# 13_-_ETHERNET_PHY.net
KiCad netlist of a schematic drawn in Altium Designer
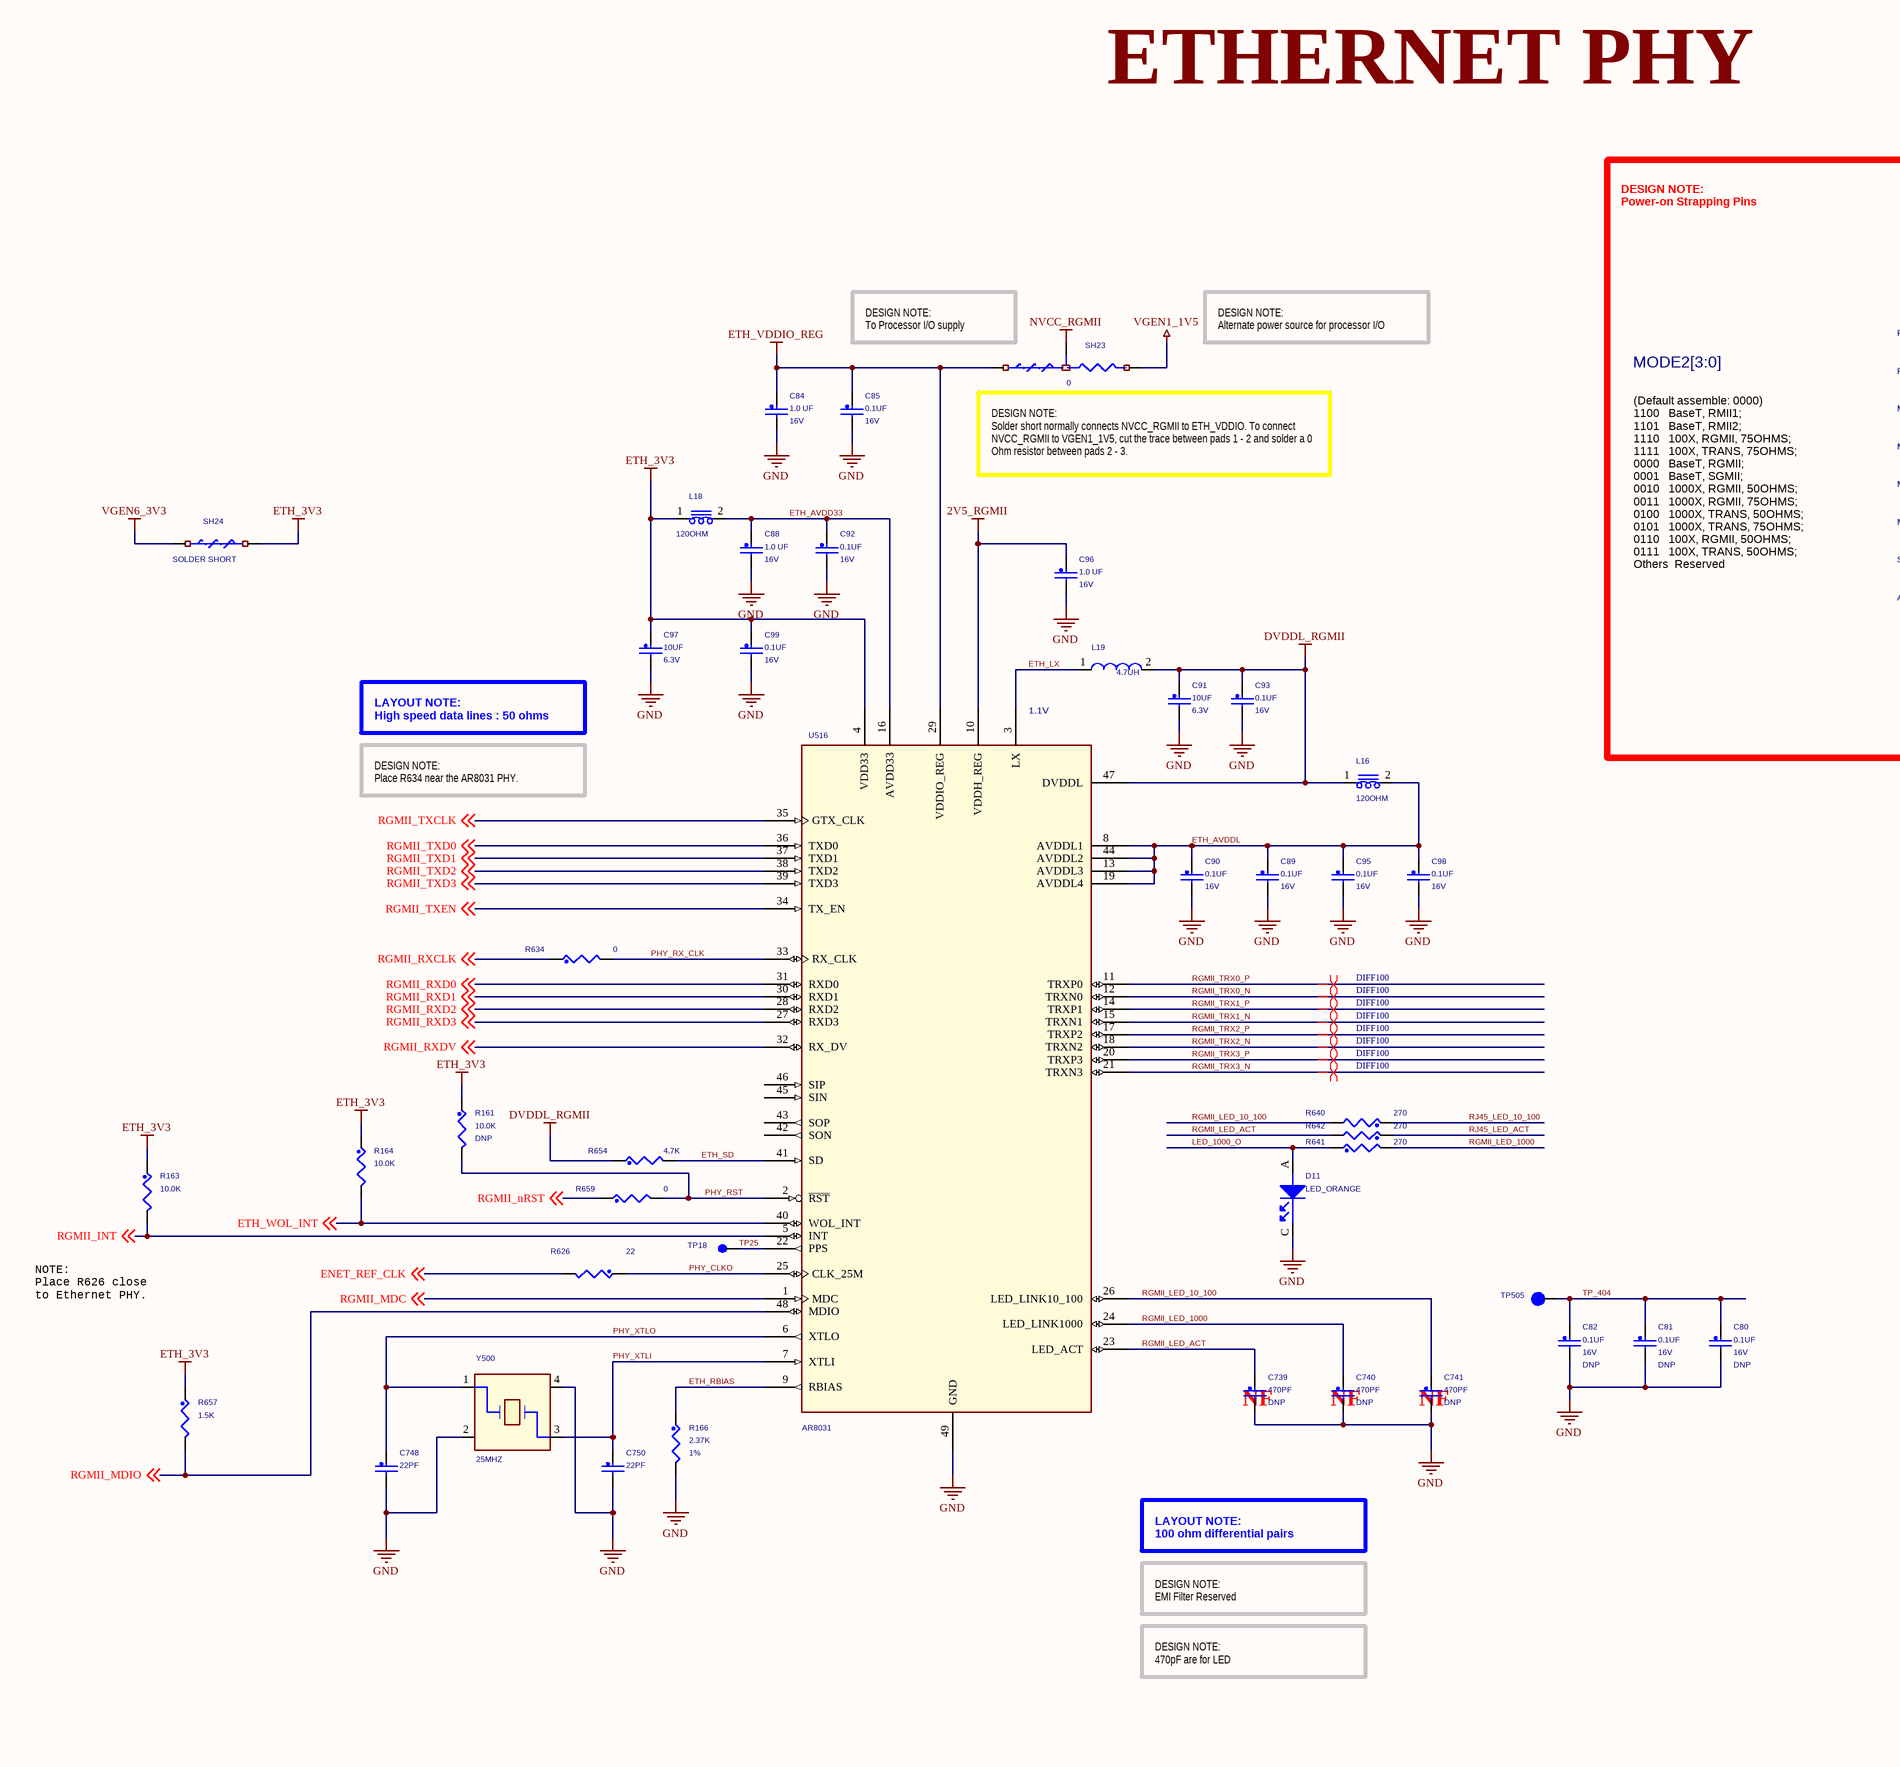
[diagram p0: [13] - ETHERNET PHY.SchDoc, left]
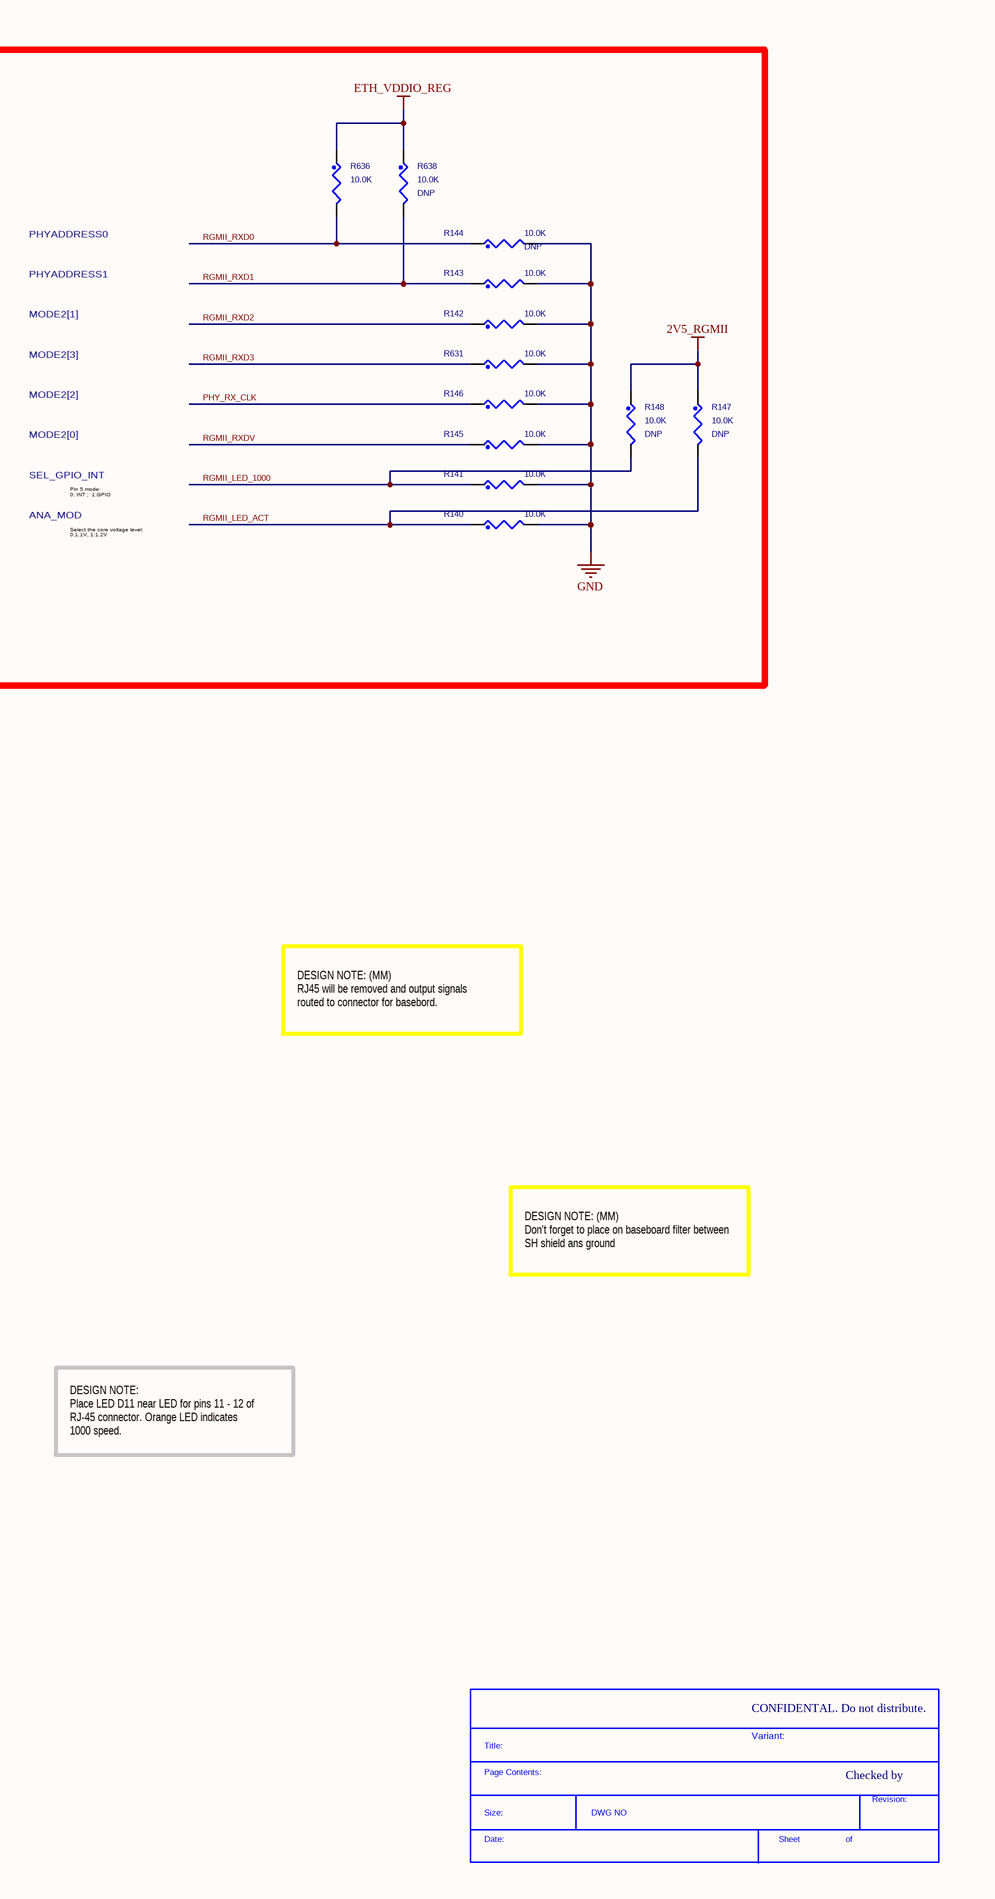
[diagram p1: [13] - ETHERNET PHY.SchDoc, right]

(export (version "E")
  (design (tool "Eeschema 10.0.6"))
  (components
    (comp (ref "*") (value "SDTitleBlock") (libsource (lib "*") (part "SDTitleBlock")))
    (comp (ref "C80")
      (value "0.1UF")
      (description "CAP CER 0.1UF 16V 10% X7R 0402")
      (fields
        (field (name "WVDC") "16V")
        (field (name "ASSY_OPT") "DNP")
        (field (name "TOLERANCE") "10%")
        (field (name "VOLTAGE") "16V")
      )
      (libsource (lib "*") (part "CAP_NP"))
    )
    (comp (ref "C81")
      (value "0.1UF")
      (description "CAP CER 0.1UF 16V 10% X7R 0402")
      (fields
        (field (name "WVDC") "16V")
        (field (name "ASSY_OPT") "DNP")
        (field (name "TOLERANCE") "10%")
        (field (name "VOLTAGE") "16V")
      )
      (libsource (lib "*") (part "CAP_NP"))
    )
    (comp (ref "C82")
      (value "0.1UF")
      (description "CAP CER 0.1UF 16V 10% X7R 0402")
      (fields
        (field (name "WVDC") "16V")
        (field (name "ASSY_OPT") "DNP")
        (field (name "TOLERANCE") "10%")
        (field (name "VOLTAGE") "16V")
      )
      (libsource (lib "*") (part "CAP_NP"))
    )
    (comp (ref "C84")
      (value "1.0 UF")
      (description "CAP CER 1.0UF 16V 10% X7R 0603")
      (fields (field (name "TOLERANCE") "10%") (field (name "WVDC") "16V") (field (name "VOLTAGE") "16V"))
      (libsource (lib "*") (part "CAP_NP"))
    )
    (comp (ref "C85")
      (value "0.1UF")
      (description "CAP CER 0.1UF 16V 10% X7R 0402")
      (fields (field (name "TOLERANCE") "10%") (field (name "WVDC") "16V") (field (name "VOLTAGE") "16V"))
      (libsource (lib "*") (part "CAP_NP"))
    )
    (comp (ref "C88")
      (value "1.0 UF")
      (description "CAP CER 1.0UF 16V 10% X7R 0603")
      (fields (field (name "TOLERANCE") "10%") (field (name "WVDC") "16V") (field (name "VOLTAGE") "16V"))
      (libsource (lib "*") (part "CAP_NP"))
    )
    (comp (ref "C89")
      (value "0.1UF")
      (description "CAP CER 0.1UF 16V 10% X7R 0402")
      (fields (field (name "TOLERANCE") "10%") (field (name "WVDC") "16V") (field (name "VOLTAGE") "16V"))
      (libsource (lib "*") (part "CAP_NP"))
    )
    (comp (ref "C90")
      (value "0.1UF")
      (description "CAP CER 0.1UF 16V 10% X7R 0402")
      (fields (field (name "TOLERANCE") "10%") (field (name "WVDC") "16V") (field (name "VOLTAGE") "16V"))
      (libsource (lib "*") (part "CAP_NP"))
    )
    (comp (ref "C91")
      (value "10UF")
      (description "CAP CER 10UF 6.3V 10% X5R 0603")
      (fields (field (name "TOLERANCE") "10%") (field (name "WVDC") "6.3V") (field (name "VOLTAGE") "6.3V"))
      (libsource (lib "*") (part "CAP_NP"))
    )
    (comp (ref "C92")
      (value "0.1UF")
      (description "CAP CER 0.1UF 16V 10% X7R 0402")
      (fields (field (name "TOLERANCE") "10%") (field (name "WVDC") "16V") (field (name "VOLTAGE") "16V"))
      (libsource (lib "*") (part "CAP_NP"))
    )
    (comp (ref "C93")
      (value "0.1UF")
      (description "CAP CER 0.1UF 16V 10% X7R 0402")
      (fields (field (name "TOLERANCE") "10%") (field (name "WVDC") "16V") (field (name "VOLTAGE") "16V"))
      (libsource (lib "*") (part "CAP_NP"))
    )
    (comp (ref "C95")
      (value "0.1UF")
      (description "CAP CER 0.1UF 16V 10% X7R 0402")
      (fields (field (name "TOLERANCE") "10%") (field (name "WVDC") "16V") (field (name "VOLTAGE") "16V"))
      (libsource (lib "*") (part "CAP_NP"))
    )
    (comp (ref "C96")
      (value "1.0 UF")
      (description "CAP CER 1.0UF 16V 10% X7R 0603")
      (fields (field (name "TOLERANCE") "10%") (field (name "WVDC") "16V") (field (name "VOLTAGE") "16V"))
      (libsource (lib "*") (part "CAP_NP"))
    )
    (comp (ref "C97")
      (value "10UF")
      (description "CAP CER 10UF 6.3V 10% X5R 0603")
      (fields (field (name "TOLERANCE") "10%") (field (name "WVDC") "6.3V") (field (name "VOLTAGE") "6.3V"))
      (libsource (lib "*") (part "CAP_NP"))
    )
    (comp (ref "C98")
      (value "0.1UF")
      (description "CAP CER 0.1UF 16V 10% X7R 0402")
      (fields (field (name "TOLERANCE") "10%") (field (name "WVDC") "16V") (field (name "VOLTAGE") "16V"))
      (libsource (lib "*") (part "CAP_NP"))
    )
    (comp (ref "C99")
      (value "0.1UF")
      (description "CAP CER 0.1UF 16V 10% X7R 0402")
      (fields (field (name "TOLERANCE") "10%") (field (name "WVDC") "16V") (field (name "VOLTAGE") "16V"))
      (libsource (lib "*") (part "CAP_NP"))
    )
    (comp (ref "C739")
      (value "470PF")
      (description "CAP CER 470PF 50V 10% X7R 0402")
      (fields (field (name "TOLERANCE") "10%") (field (name "ASSY_OPT") "DNP") (field (name "VOLTAGE") "50V"))
      (libsource (lib "*") (part "CAP_NP"))
    )
    (comp (ref "C740")
      (value "470PF")
      (description "CAP CER 470PF 50V 10% X7R 0402")
      (fields (field (name "TOLERANCE") "10%") (field (name "ASSY_OPT") "DNP") (field (name "VOLTAGE") "50V"))
      (libsource (lib "*") (part "CAP_NP"))
    )
    (comp (ref "C741")
      (value "470PF")
      (description "CAP CER 470PF 50V 10% X7R 0402")
      (fields (field (name "TOLERANCE") "10%") (field (name "ASSY_OPT") "DNP") (field (name "VOLTAGE") "50V"))
      (libsource (lib "*") (part "CAP_NP"))
    )
    (comp (ref "C748")
      (value "22PF")
      (description "CAP CER 22PF 50V 5% C0G 0402")
      (fields (field (name "TOLERANCE") "5%") (field (name "VOLTAGE") "50V"))
      (libsource (lib "*") (part "CAP_NP"))
    )
    (comp (ref "C750")
      (value "22PF")
      (description "CAP CER 22PF 50V 5% C0G 0402")
      (fields (field (name "TOLERANCE") "5%") (field (name "VOLTAGE") "50V"))
      (libsource (lib "*") (part "CAP_NP"))
    )
    (comp (ref "D11")
      (value "LED_ORANGE")
      (description "LED SUPER BRIGHT ORANGE SMD 0603")
      (libsource (lib "*") (part "LED"))
    )
    (comp (ref "L16")
      (value "120OHM")
      (description "IND FER BEAD 120OHM@100MHZ 2A 25% 0603")
      (fields (field (name "TOLERANCE") "25%"))
      (libsource (lib "*") (part "BEAD_0"))
    )
    (comp (ref "L18")
      (value "120OHM")
      (description "IND FER BEAD 120OHM@100MHZ 2A 25% 0603")
      (fields (field (name "TOLERANCE") "25%"))
      (libsource (lib "*") (part "BEAD_0"))
    )
    (comp (ref "L19")
      (value "4.7UH")
      (description "IND PWR 4.7UH@1MHZ 1A 20% SMD")
      (fields (field (name "TOLERANCE") "20%"))
      (libsource (lib "*") (part "INDUCTOR"))
    )
    (comp (ref "R140")
      (value "10.0K")
      (description "RES MF 10.0K 1/16W 1% 0402")
      (fields (field (name "TOLERANCE") "1%"))
      (libsource (lib "*") (part "RES"))
    )
    (comp (ref "R141")
      (value "10.0K")
      (description "RES MF 10.0K 1/16W 1% 0402")
      (fields (field (name "TOLERANCE") "1%"))
      (libsource (lib "*") (part "RES"))
    )
    (comp (ref "R142")
      (value "10.0K")
      (description "RES MF 10.0K 1/16W 1% 0402")
      (fields (field (name "TOLERANCE") "1%"))
      (libsource (lib "*") (part "RES"))
    )
    (comp (ref "R143")
      (value "10.0K")
      (description "RES MF 10.0K 1/16W 1% 0402")
      (fields (field (name "TOLERANCE") "1%"))
      (libsource (lib "*") (part "RES"))
    )
    (comp (ref "R144")
      (value "10.0K")
      (description "RES MF 10.0K 1/16W 1% 0402")
      (fields (field (name "TOLERANCE") "1%") (field (name "ASSY_OPT") "DNP"))
      (libsource (lib "*") (part "RES"))
    )
    (comp (ref "R145")
      (value "10.0K")
      (description "RES MF 10.0K 1/16W 1% 0402")
      (fields (field (name "TOLERANCE") "1%"))
      (libsource (lib "*") (part "RES"))
    )
    (comp (ref "R146")
      (value "10.0K")
      (description "RES MF 10.0K 1/16W 1% 0402")
      (fields (field (name "TOLERANCE") "1%"))
      (libsource (lib "*") (part "RES"))
    )
    (comp (ref "R147")
      (value "10.0K")
      (description "RES MF 10.0K 1/16W 1% 0402")
      (fields (field (name "TOLERANCE") "1%") (field (name "ASSY_OPT") "DNP"))
      (libsource (lib "*") (part "RES"))
    )
    (comp (ref "R148")
      (value "10.0K")
      (description "RES MF 10.0K 1/16W 1% 0402")
      (fields (field (name "TOLERANCE") "1%") (field (name "ASSY_OPT") "DNP"))
      (libsource (lib "*") (part "RES"))
    )
    (comp (ref "R161")
      (value "10.0K")
      (description "RES MF 10.0K 1/16W 1% 0402")
      (fields (field (name "ASSY_OPT") "DNP") (field (name "TOLERANCE") "1%"))
      (libsource (lib "*") (part "RES"))
    )
    (comp (ref "R163")
      (value "10.0K")
      (description "RES MF 10.0K 1/16W 1% 0402")
      (fields (field (name "TOLERANCE") "1%"))
      (libsource (lib "*") (part "RES"))
    )
    (comp (ref "R164")
      (value "10.0K")
      (description "RES MF 10.0K 1/16W 1% 0402")
      (fields (field (name "TOLERANCE") "1%"))
      (libsource (lib "*") (part "RES"))
    )
    (comp (ref "R166")
      (value "2.37K")
      (description "RES MF 2.37K  1/16W 1% 0402")
      (fields (field (name "TOLERANCE") "1%"))
      (libsource (lib "*") (part "RES"))
    )
    (comp (ref "R626")
      (value "22")
      (description "RES MF 22.0 OHM 1/10W 1% 0603")
      (fields (field (name "TOLERANCE") "1%"))
      (libsource (lib "*") (part "RES"))
    )
    (comp (ref "R631")
      (value "10.0K")
      (description "RES MF 10.0K 1/16W 1% 0402")
      (fields (field (name "TOLERANCE") "1%"))
      (libsource (lib "*") (part "RES"))
    )
    (comp (ref "R634")
      (value "0")
      (description "RES MF ZERO OHM 1/10W -- 0402")
      (libsource (lib "*") (part "RES"))
    )
    (comp (ref "R636")
      (value "10.0K")
      (description "RES MF 10.0K 1/16W 1% 0402")
      (fields (field (name "TOLERANCE") "1%"))
      (libsource (lib "*") (part "RES"))
    )
    (comp (ref "R638")
      (value "10.0K")
      (description "RES MF 10.0K 1/16W 1% 0402")
      (fields (field (name "ASSY_OPT") "DNP") (field (name "TOLERANCE") "1%"))
      (libsource (lib "*") (part "RES"))
    )
    (comp (ref "R640")
      (value "270")
      (description "RES MF 270 OHM 1/16W 5% 0402")
      (fields (field (name "TOLERANCE") "5%"))
      (libsource (lib "*") (part "RES"))
    )
    (comp (ref "R641")
      (value "270")
      (description "RES MF 270 OHM 1/16W 5% 0402")
      (fields (field (name "TOLERANCE") "5%"))
      (libsource (lib "*") (part "RES"))
    )
    (comp (ref "R642")
      (value "270")
      (description "RES MF 270 OHM 1/16W 5% 0402")
      (fields (field (name "TOLERANCE") "5%"))
      (libsource (lib "*") (part "RES"))
    )
    (comp (ref "R654")
      (value "4.7K")
      (description "RES MF 4.70K 1/16W 1% 0402")
      (fields (field (name "TOLERANCE") "1%"))
      (libsource (lib "*") (part "RES"))
    )
    (comp (ref "R657")
      (value "1.5K")
      (description "RES MF 1.50K 1/16W 1% 0402")
      (fields (field (name "TOLERANCE") "1%"))
      (libsource (lib "*") (part "RES"))
    )
    (comp (ref "R659")
      (value "0")
      (description "RES MF ZERO OHM 1/10W -- 0402")
      (libsource (lib "*") (part "RES"))
    )
    (comp (ref "SH23")
      (value "0")
      (description "ZERO OHM CUT TRACE 0603 PADS; NO PART TO ORDER")
      (libsource (lib "*") (part "RES_SHORT-3_1TO2"))
    )
    (comp (ref "SH24")
      (value "SOLDER SHORT")
      (description "SOLDER SHORT 0805  SMT NO PART TO ORDER")
      (libsource (lib "*") (part "RES_SHORT-2"))
    )
    (comp (ref "TP18")
      (value "TEST POINT")
      (description "TEST POINT PAD 35 MIL SMT, NO PART TO ORDER")
      (libsource (lib "*") (part "Test pad"))
    )
    (comp (ref "TP505")
      (value "tpad_020")
      (description "TEST POINT PAD 0.5MM DIA SMT, NO PART TO ORDER")
      (libsource (lib "*") (part "TESTLOOP"))
    )
    (comp (ref "U516")
      (value "AR8031")
      (description "IC XCVR ETHERNET PHY 10/100/1000G-BIT 3.3V QFN48")
      (libsource (lib "*") (part "AR8031_QFN48"))
    )
    (comp (ref "Y500")
      (value "25MHZ")
      (description "XTAL 25MHZ -- -- SMT")
      (libsource (lib "*") (part "XTAL_13Y"))
    )
  )
  (nets
    (net (code "1") (name "/ETH_AVDD33") (class "Default")
      (node (ref "C88") (pin "1") (pinfunction "1_1") (pintype "passive"))
      (node (ref "C92") (pin "1") (pinfunction "1_1") (pintype "passive"))
      (node (ref "L18") (pin "2") (pinfunction "2_2") (pintype "passive"))
      (node (ref "U516") (pin "16") (pinfunction "AVDD33_16") (pintype "power_in"))
    )
    (net (code "2") (name "/ETH_AVDDL") (class "Default")
      (node (ref "C89") (pin "1") (pinfunction "1_1") (pintype "passive"))
      (node (ref "C90") (pin "1") (pinfunction "1_1") (pintype "passive"))
      (node (ref "C95") (pin "1") (pinfunction "1_1") (pintype "passive"))
      (node (ref "C98") (pin "1") (pinfunction "1_1") (pintype "passive"))
      (node (ref "L16") (pin "2") (pinfunction "2_2") (pintype "passive"))
      (node (ref "U516") (pin "13") (pinfunction "AVDDL3_13") (pintype "power_in"))
      (node (ref "U516") (pin "19") (pinfunction "AVDDL4_19") (pintype "power_in"))
      (node (ref "U516") (pin "44") (pinfunction "AVDDL2_44") (pintype "power_in"))
      (node (ref "U516") (pin "8") (pinfunction "AVDDL1_8") (pintype "power_in"))
    )
    (net (code "3") (name "/ETH_LX") (class "Default")
      (node (ref "L19") (pin "1") (pinfunction "1_1") (pintype "passive"))
      (node (ref "U516") (pin "3") (pinfunction "LX_3") (pintype "power_in"))
    )
    (net (code "4") (name "/ETH_RBIAS") (class "Default")
      (node (ref "R166") (pin "1") (pinfunction "1_1") (pintype "passive"))
      (node (ref "U516") (pin "9") (pinfunction "RBIAS_9") (pintype "output"))
    )
    (net (code "5") (name "/ETH_SD") (class "Default")
      (node (ref "R654") (pin "2") (pinfunction "2_2") (pintype "passive"))
      (node (ref "U516") (pin "41") (pinfunction "SD_41") (pintype "input"))
    )
    (net (code "6") (name "/LED_1000_O") (class "Default")
      (node (ref "D11") (pin "A") (pinfunction "ANODE_A") (pintype "passive"))
      (node (ref "R641") (pin "1") (pinfunction "1_1") (pintype "passive"))
    )
    (net (code "7") (name "/PHY_CLKO") (class "Default")
      (node (ref "R626") (pin "1") (pinfunction "1_1") (pintype "passive"))
      (node (ref "U516") (pin "25") (pinfunction "CLK_25M_25") (pintype "bidirectional"))
    )
    (net (code "8") (name "/PHY_RST") (class "Default")
      (node (ref "R161") (pin "2") (pinfunction "2_2") (pintype "passive"))
      (node (ref "R659") (pin "2") (pinfunction "2_2") (pintype "passive"))
      (node (ref "U516") (pin "2") (pinfunction "~{RST}_2") (pintype "input"))
    )
    (net (code "9") (name "/PHY_RX_CLK") (class "Default")
      (node (ref "R146") (pin "1") (pinfunction "1_1") (pintype "passive"))
      (node (ref "R634") (pin "2") (pinfunction "2_2") (pintype "passive"))
      (node (ref "U516") (pin "33") (pinfunction "RX_CLK_33") (pintype "bidirectional"))
    )
    (net (code "10") (name "/PHY_XTLI") (class "Default")
      (node (ref "C750") (pin "1") (pinfunction "1_1") (pintype "passive"))
      (node (ref "U516") (pin "7") (pinfunction "XTLI_7") (pintype "input"))
      (node (ref "Y500") (pin "3") (pinfunction "3_3") (pintype "passive"))
    )
    (net (code "11") (name "/PHY_XTLO") (class "Default")
      (node (ref "C748") (pin "1") (pinfunction "1_1") (pintype "passive"))
      (node (ref "U516") (pin "6") (pinfunction "XTLO_6") (pintype "output"))
      (node (ref "Y500") (pin "1") (pinfunction "1_1") (pintype "passive"))
    )
    (net (code "12") (name "/RGMII_LED_10_100") (class "Default")
      (node (ref "C741") (pin "1") (pinfunction "1_1") (pintype "passive"))
      (node (ref "R640") (pin "2") (pinfunction "2_2") (pintype "passive"))
      (node (ref "U516") (pin "26") (pinfunction "LED_LINK10_100_26") (pintype "bidirectional"))
    )
    (net (code "13") (name "/RGMII_LED_1000") (class "Default")
      (node (ref "C740") (pin "1") (pinfunction "1_1") (pintype "passive"))
      (node (ref "R141") (pin "1") (pinfunction "1_1") (pintype "passive"))
      (node (ref "R148") (pin "2") (pinfunction "2_2") (pintype "passive"))
      (node (ref "R641") (pin "2") (pinfunction "2_2") (pintype "passive"))
      (node (ref "U516") (pin "24") (pinfunction "LED_LINK1000_24") (pintype "bidirectional"))
    )
    (net (code "14") (name "/RGMII_LED_ACT") (class "Default")
      (node (ref "C739") (pin "1") (pinfunction "1_1") (pintype "passive"))
      (node (ref "R140") (pin "1") (pinfunction "1_1") (pintype "passive"))
      (node (ref "R147") (pin "2") (pinfunction "2_2") (pintype "passive"))
      (node (ref "R642") (pin "2") (pinfunction "2_2") (pintype "passive"))
      (node (ref "U516") (pin "23") (pinfunction "LED_ACT_23") (pintype "bidirectional"))
    )
    (net (code "15") (name "/RGMII_TRX0_N") (class "Default")
      (node (ref "U516") (pin "12") (pinfunction "TRXN0_12") (pintype "bidirectional"))
    )
    (net (code "16") (name "/RGMII_TRX0_P") (class "Default")
      (node (ref "U516") (pin "11") (pinfunction "TRXP0_11") (pintype "bidirectional"))
    )
    (net (code "17") (name "/RGMII_TRX1_N") (class "Default")
      (node (ref "U516") (pin "15") (pinfunction "TRXN1_15") (pintype "bidirectional"))
    )
    (net (code "18") (name "/RGMII_TRX1_P") (class "Default")
      (node (ref "U516") (pin "14") (pinfunction "TRXP1_14") (pintype "bidirectional"))
    )
    (net (code "19") (name "/RGMII_TRX2_N") (class "Default")
      (node (ref "U516") (pin "18") (pinfunction "TRXN2_18") (pintype "bidirectional"))
    )
    (net (code "20") (name "/RGMII_TRX2_P") (class "Default")
      (node (ref "U516") (pin "17") (pinfunction "TRXP2_17") (pintype "bidirectional"))
    )
    (net (code "21") (name "/RGMII_TRX3_N") (class "Default")
      (node (ref "U516") (pin "21") (pinfunction "TRXN3_21") (pintype "bidirectional"))
    )
    (net (code "22") (name "/RGMII_TRX3_P") (class "Default")
      (node (ref "U516") (pin "20") (pinfunction "TRXP3_20") (pintype "bidirectional"))
    )
    (net (code "23") (name "/RJ45_LED_10_100") (class "Default")
      (node (ref "R640") (pin "1") (pinfunction "1_1") (pintype "passive"))
    )
    (net (code "24") (name "/RJ45_LED_ACT") (class "Default")
      (node (ref "R642") (pin "1") (pinfunction "1_1") (pintype "passive"))
    )
    (net (code "25") (name "/TP25") (class "Default")
      (node (ref "TP18") (pin "1") (pinfunction "Pin1_1") (pintype "passive"))
      (node (ref "U516") (pin "22") (pinfunction "PPS_22") (pintype "output"))
    )
    (net (code "26") (name "/TP_404") (class "Default")
      (node (ref "C80") (pin "1") (pinfunction "1_1") (pintype "passive"))
      (node (ref "C81") (pin "1") (pinfunction "1_1") (pintype "passive"))
      (node (ref "C82") (pin "1") (pinfunction "1_1") (pintype "passive"))
      (node (ref "TP505") (pin "1") (pinfunction "Pin1_1") (pintype "passive"))
    )
    (net (code "27") (name "2V5_RGMII") (class "Default")
      (node (ref "C96") (pin "1") (pinfunction "1_1") (pintype "passive"))
      (node (ref "R147") (pin "1") (pinfunction "1_1") (pintype "passive"))
      (node (ref "R148") (pin "1") (pinfunction "1_1") (pintype "passive"))
      (node (ref "U516") (pin "10") (pinfunction "VDDH_REG_10") (pintype "power_in"))
    )
    (net (code "28") (name "DVDDL_RGMII") (class "Default")
      (node (ref "C91") (pin "1") (pinfunction "1_1") (pintype "passive"))
      (node (ref "C93") (pin "1") (pinfunction "1_1") (pintype "passive"))
      (node (ref "L16") (pin "1") (pinfunction "1_1") (pintype "passive"))
      (node (ref "L19") (pin "2") (pinfunction "2_2") (pintype "passive"))
      (node (ref "R654") (pin "1") (pinfunction "1_1") (pintype "passive"))
      (node (ref "U516") (pin "47") (pinfunction "DVDDL_47") (pintype "power_in"))
    )
    (net (code "29") (name "ENET_REF_CLK") (class "Default")
      (node (ref "R626") (pin "2") (pinfunction "2_2") (pintype "passive"))
    )
    (net (code "30") (name "ETH_3V3") (class "Default")
      (node (ref "C97") (pin "1") (pinfunction "1_1") (pintype "passive"))
      (node (ref "C99") (pin "1") (pinfunction "1_1") (pintype "passive"))
      (node (ref "L18") (pin "1") (pinfunction "1_1") (pintype "passive"))
      (node (ref "R161") (pin "1") (pinfunction "1_1") (pintype "passive"))
      (node (ref "R163") (pin "1") (pinfunction "1_1") (pintype "passive"))
      (node (ref "R164") (pin "1") (pinfunction "1_1") (pintype "passive"))
      (node (ref "R657") (pin "1") (pinfunction "1_1") (pintype "passive"))
      (node (ref "SH24") (pin "2") (pinfunction "2_2") (pintype "passive"))
      (node (ref "U516") (pin "4") (pinfunction "VDD33_4") (pintype "power_in"))
    )
    (net (code "31") (name "ETH_VDDIO_REG") (class "Default")
      (node (ref "C84") (pin "1") (pinfunction "1_1") (pintype "passive"))
      (node (ref "C85") (pin "1") (pinfunction "1_1") (pintype "passive"))
      (node (ref "R636") (pin "1") (pinfunction "1_1") (pintype "passive"))
      (node (ref "R638") (pin "1") (pinfunction "1_1") (pintype "passive"))
      (node (ref "SH23") (pin "1") (pinfunction "1_1") (pintype "passive"))
      (node (ref "U516") (pin "29") (pinfunction "VDDIO_REG_29") (pintype "power_in"))
    )
    (net (code "32") (name "ETH_WOL_INT") (class "Default")
      (node (ref "R164") (pin "2") (pinfunction "2_2") (pintype "passive"))
      (node (ref "U516") (pin "40") (pinfunction "WOL_INT_40") (pintype "bidirectional"))
    )
    (net (code "33") (name "GND") (class "Default")
      (node (ref "C739") (pin "2") (pinfunction "2_2") (pintype "passive"))
      (node (ref "C740") (pin "2") (pinfunction "2_2") (pintype "passive"))
      (node (ref "C741") (pin "2") (pinfunction "2_2") (pintype "passive"))
      (node (ref "C748") (pin "2") (pinfunction "2_2") (pintype "passive"))
      (node (ref "C750") (pin "2") (pinfunction "2_2") (pintype "passive"))
      (node (ref "C80") (pin "2") (pinfunction "2_2") (pintype "passive"))
      (node (ref "C81") (pin "2") (pinfunction "2_2") (pintype "passive"))
      (node (ref "C82") (pin "2") (pinfunction "2_2") (pintype "passive"))
      (node (ref "C84") (pin "2") (pinfunction "2_2") (pintype "passive"))
      (node (ref "C85") (pin "2") (pinfunction "2_2") (pintype "passive"))
      (node (ref "C88") (pin "2") (pinfunction "2_2") (pintype "passive"))
      (node (ref "C89") (pin "2") (pinfunction "2_2") (pintype "passive"))
      (node (ref "C90") (pin "2") (pinfunction "2_2") (pintype "passive"))
      (node (ref "C91") (pin "2") (pinfunction "2_2") (pintype "passive"))
      (node (ref "C92") (pin "2") (pinfunction "2_2") (pintype "passive"))
      (node (ref "C93") (pin "2") (pinfunction "2_2") (pintype "passive"))
      (node (ref "C95") (pin "2") (pinfunction "2_2") (pintype "passive"))
      (node (ref "C96") (pin "2") (pinfunction "2_2") (pintype "passive"))
      (node (ref "C97") (pin "2") (pinfunction "2_2") (pintype "passive"))
      (node (ref "C98") (pin "2") (pinfunction "2_2") (pintype "passive"))
      (node (ref "C99") (pin "2") (pinfunction "2_2") (pintype "passive"))
      (node (ref "D11") (pin "C") (pinfunction "CATHODE_C") (pintype "passive"))
      (node (ref "R140") (pin "2") (pinfunction "2_2") (pintype "passive"))
      (node (ref "R141") (pin "2") (pinfunction "2_2") (pintype "passive"))
      (node (ref "R142") (pin "2") (pinfunction "2_2") (pintype "passive"))
      (node (ref "R143") (pin "2") (pinfunction "2_2") (pintype "passive"))
      (node (ref "R144") (pin "2") (pinfunction "2_2") (pintype "passive"))
      (node (ref "R145") (pin "2") (pinfunction "2_2") (pintype "passive"))
      (node (ref "R146") (pin "2") (pinfunction "2_2") (pintype "passive"))
      (node (ref "R166") (pin "2") (pinfunction "2_2") (pintype "passive"))
      (node (ref "R631") (pin "2") (pinfunction "2_2") (pintype "passive"))
      (node (ref "U516") (pin "49") (pinfunction "GND_49") (pintype "power_in"))
      (node (ref "Y500") (pin "2") (pinfunction "2_2") (pintype "power_in"))
      (node (ref "Y500") (pin "4") (pinfunction "4_4") (pintype "power_in"))
    )
    (net (code "34") (name "NVCC_RGMII") (class "Default")
      (node (ref "SH23") (pin "2") (pinfunction "2_2") (pintype "passive"))
    )
    (net (code "35") (name "RGMII_INT") (class "Default")
      (node (ref "R163") (pin "2") (pinfunction "2_2") (pintype "passive"))
      (node (ref "U516") (pin "5") (pinfunction "INT_5") (pintype "bidirectional"))
    )
    (net (code "36") (name "RGMII_MDC") (class "Default")
      (node (ref "U516") (pin "1") (pinfunction "MDC_1") (pintype "input"))
    )
    (net (code "37") (name "RGMII_MDIO") (class "Default")
      (node (ref "R657") (pin "2") (pinfunction "2_2") (pintype "passive"))
      (node (ref "U516") (pin "48") (pinfunction "MDIO_48") (pintype "bidirectional"))
    )
    (net (code "38") (name "RGMII_RXCLK") (class "Default")
      (node (ref "R634") (pin "1") (pinfunction "1_1") (pintype "passive"))
    )
    (net (code "39") (name "RGMII_RXD0") (class "Default")
      (node (ref "R144") (pin "1") (pinfunction "1_1") (pintype "passive"))
      (node (ref "R636") (pin "2") (pinfunction "2_2") (pintype "passive"))
      (node (ref "U516") (pin "31") (pinfunction "RXD0_31") (pintype "bidirectional"))
    )
    (net (code "40") (name "RGMII_RXD1") (class "Default")
      (node (ref "R143") (pin "1") (pinfunction "1_1") (pintype "passive"))
      (node (ref "R638") (pin "2") (pinfunction "2_2") (pintype "passive"))
      (node (ref "U516") (pin "30") (pinfunction "RXD1_30") (pintype "bidirectional"))
    )
    (net (code "41") (name "RGMII_RXD2") (class "Default")
      (node (ref "R142") (pin "1") (pinfunction "1_1") (pintype "passive"))
      (node (ref "U516") (pin "28") (pinfunction "RXD2_28") (pintype "bidirectional"))
    )
    (net (code "42") (name "RGMII_RXD3") (class "Default")
      (node (ref "R631") (pin "1") (pinfunction "1_1") (pintype "passive"))
      (node (ref "U516") (pin "27") (pinfunction "RXD3_27") (pintype "bidirectional"))
    )
    (net (code "43") (name "RGMII_RXDV") (class "Default")
      (node (ref "R145") (pin "1") (pinfunction "1_1") (pintype "passive"))
      (node (ref "U516") (pin "32") (pinfunction "RX_DV_32") (pintype "bidirectional"))
    )
    (net (code "44") (name "RGMII_TXCLK") (class "Default")
      (node (ref "U516") (pin "35") (pinfunction "GTX_CLK_35") (pintype "input"))
    )
    (net (code "45") (name "RGMII_TXD0") (class "Default")
      (node (ref "U516") (pin "36") (pinfunction "TXD0_36") (pintype "input"))
    )
    (net (code "46") (name "RGMII_TXD1") (class "Default")
      (node (ref "U516") (pin "37") (pinfunction "TXD1_37") (pintype "input"))
    )
    (net (code "47") (name "RGMII_TXD2") (class "Default")
      (node (ref "U516") (pin "38") (pinfunction "TXD2_38") (pintype "input"))
    )
    (net (code "48") (name "RGMII_TXD3") (class "Default")
      (node (ref "U516") (pin "39") (pinfunction "TXD3_39") (pintype "input"))
    )
    (net (code "49") (name "RGMII_TXEN") (class "Default")
      (node (ref "U516") (pin "34") (pinfunction "TX_EN_34") (pintype "input"))
    )
    (net (code "50") (name "RGMII_nRST") (class "Default")
      (node (ref "R659") (pin "1") (pinfunction "1_1") (pintype "passive"))
    )
    (net (code "51") (name "VGEN1_1V5") (class "Default")
      (node (ref "SH23") (pin "3") (pinfunction "3_3") (pintype "passive"))
    )
    (net (code "52") (name "VGEN6_3V3") (class "Default")
      (node (ref "SH24") (pin "1") (pinfunction "1_1") (pintype "passive"))
    )
    (net (code "53") (name "unconnected-(U516-SIN-Pad45)") (class "Default")
      (node (ref "U516") (pin "45") (pinfunction "SIN_45") (pintype "input"))
    )
    (net (code "54") (name "unconnected-(U516-SIP-Pad46)") (class "Default")
      (node (ref "U516") (pin "46") (pinfunction "SIP_46") (pintype "input"))
    )
    (net (code "55") (name "unconnected-(U516-SON-Pad42)") (class "Default")
      (node (ref "U516") (pin "42") (pinfunction "SON_42") (pintype "output"))
    )
    (net (code "56") (name "unconnected-(U516-SOP-Pad43)") (class "Default")
      (node (ref "U516") (pin "43") (pinfunction "SOP_43") (pintype "output"))
    )
  )
)
